# base.net
KiCad netlist of a schematic drawn in EAGLE
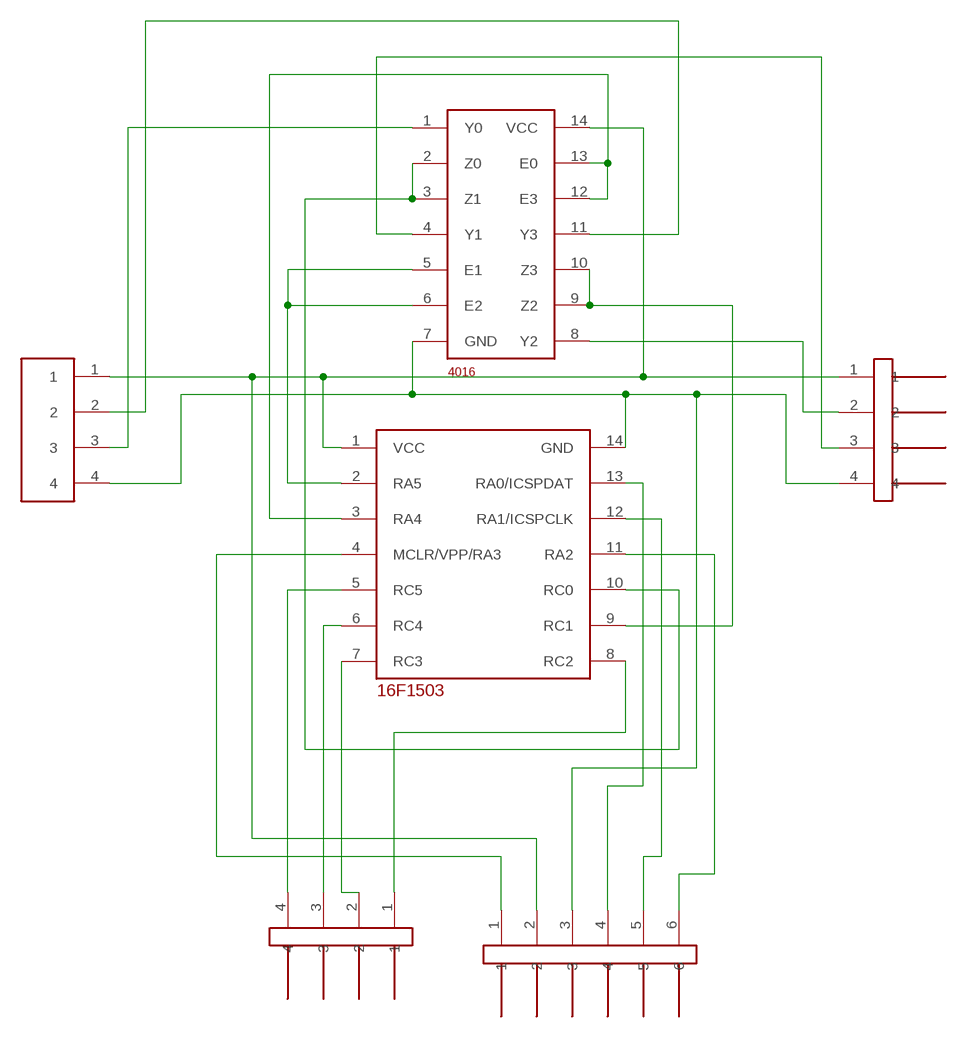
[diagram p0: schematic, sheet 1]

(export (version "E")
  (design (tool "Eeschema 10.0.6"))
  (components
    (comp (ref "U$1")
      (value "16F1503")
      (footprint "eagle-import:16F1503")
      (libsource (lib "eagle-import") (part "16F1503"))
    )
    (comp (ref "U$2")
      (value "4016")
      (footprint "eagle-import:SO14")
      (libsource (lib "eagle-import") (part "4016"))
    )
    (comp (ref "U$3")
      (value "JUMPER4")
      (footprint "eagle-import:JUMPER4")
      (libsource (lib "eagle-import") (part "JUMPER4"))
    )
    (comp (ref "U$4")
      (value "JUMPER4F")
      (footprint "eagle-import:JUMPER4F")
      (libsource (lib "eagle-import") (part "JUMPER4F"))
    )
    (comp (ref "U$5")
      (value "JUMPER4M")
      (footprint "eagle-import:JUMPER4M")
      (libsource (lib "eagle-import") (part "JUMPER4M"))
    )
    (comp (ref "U$6")
      (value "JUMPER6M")
      (footprint "eagle-import:JUMPER6M")
      (libsource (lib "eagle-import") (part "JUMPER6M"))
    )
  )
  (nets
    (net (code "1") (name "Net-(U$1-GND)") (class "Default")
      (node (ref "U$1") (pin "14") (pinfunction "GND_14") (pintype "power_in"))
      (node (ref "U$2") (pin "7") (pinfunction "GND_7") (pintype "bidirectional"))
      (node (ref "U$3") (pin "4") (pinfunction "4_4") (pintype "bidirectional"))
      (node (ref "U$4") (pin "4") (pinfunction "4_4") (pintype "bidirectional"))
      (node (ref "U$6") (pin "3") (pinfunction "3_3") (pintype "bidirectional"))
    )
    (net (code "2") (name "Net-(U$1-MCLR{slash}VPP{slash}RA3)") (class "Default")
      (node (ref "U$1") (pin "4") (pinfunction "MCLR/VPP/RA3_4") (pintype "bidirectional"))
      (node (ref "U$6") (pin "1") (pinfunction "1_1") (pintype "bidirectional"))
    )
    (net (code "3") (name "Net-(U$1-RA0{slash}ICSPDAT)") (class "Default")
      (node (ref "U$1") (pin "13") (pinfunction "RA0/ICSPDAT_13") (pintype "bidirectional"))
      (node (ref "U$6") (pin "4") (pinfunction "4_4") (pintype "bidirectional"))
    )
    (net (code "4") (name "Net-(U$1-RA1{slash}ICSPCLK)") (class "Default")
      (node (ref "U$1") (pin "12") (pinfunction "RA1/ICSPCLK_12") (pintype "bidirectional"))
      (node (ref "U$6") (pin "5") (pinfunction "5_5") (pintype "bidirectional"))
    )
    (net (code "5") (name "Net-(U$1-RA2)") (class "Default")
      (node (ref "U$1") (pin "11") (pinfunction "RA2_11") (pintype "bidirectional"))
      (node (ref "U$6") (pin "6") (pinfunction "6_6") (pintype "bidirectional"))
    )
    (net (code "6") (name "Net-(U$1-RA4)") (class "Default")
      (node (ref "U$1") (pin "3") (pinfunction "RA4_3") (pintype "bidirectional"))
      (node (ref "U$2") (pin "12") (pinfunction "E3_12") (pintype "bidirectional"))
      (node (ref "U$2") (pin "13") (pinfunction "E0_13") (pintype "bidirectional"))
    )
    (net (code "7") (name "Net-(U$1-RA5)") (class "Default")
      (node (ref "U$1") (pin "2") (pinfunction "RA5_2") (pintype "bidirectional"))
      (node (ref "U$2") (pin "5") (pinfunction "E1_5") (pintype "bidirectional"))
      (node (ref "U$2") (pin "6") (pinfunction "E2_6") (pintype "bidirectional"))
    )
    (net (code "8") (name "Net-(U$1-RC0)") (class "Default")
      (node (ref "U$1") (pin "10") (pinfunction "RC0_10") (pintype "bidirectional"))
      (node (ref "U$2") (pin "2") (pinfunction "Z0_2") (pintype "bidirectional"))
      (node (ref "U$2") (pin "3") (pinfunction "Z1_3") (pintype "bidirectional"))
    )
    (net (code "9") (name "Net-(U$1-RC1)") (class "Default")
      (node (ref "U$1") (pin "9") (pinfunction "RC1_9") (pintype "bidirectional"))
      (node (ref "U$2") (pin "10") (pinfunction "Z3_10") (pintype "bidirectional"))
      (node (ref "U$2") (pin "9") (pinfunction "Z2_9") (pintype "bidirectional"))
    )
    (net (code "10") (name "Net-(U$1-RC2)") (class "Default")
      (node (ref "U$1") (pin "8") (pinfunction "RC2_8") (pintype "bidirectional"))
      (node (ref "U$5") (pin "1") (pinfunction "1_1") (pintype "bidirectional"))
    )
    (net (code "11") (name "Net-(U$1-RC3)") (class "Default")
      (node (ref "U$1") (pin "7") (pinfunction "RC3_7") (pintype "bidirectional"))
      (node (ref "U$5") (pin "2") (pinfunction "2_2") (pintype "bidirectional"))
    )
    (net (code "12") (name "Net-(U$1-RC4)") (class "Default")
      (node (ref "U$1") (pin "6") (pinfunction "RC4_6") (pintype "bidirectional"))
      (node (ref "U$5") (pin "3") (pinfunction "3_3") (pintype "bidirectional"))
    )
    (net (code "13") (name "Net-(U$1-RC5)") (class "Default")
      (node (ref "U$1") (pin "5") (pinfunction "RC5_5") (pintype "bidirectional"))
      (node (ref "U$5") (pin "4") (pinfunction "4_4") (pintype "bidirectional"))
    )
    (net (code "14") (name "Net-(U$1-VCC)") (class "Default")
      (node (ref "U$1") (pin "1") (pinfunction "VCC_1") (pintype "power_in"))
      (node (ref "U$2") (pin "14") (pinfunction "VCC_14") (pintype "bidirectional"))
      (node (ref "U$3") (pin "1") (pinfunction "1_1") (pintype "bidirectional"))
      (node (ref "U$4") (pin "1") (pinfunction "1_1") (pintype "bidirectional"))
      (node (ref "U$6") (pin "2") (pinfunction "2_2") (pintype "bidirectional"))
    )
    (net (code "15") (name "Net-(U$2-Y0)") (class "Default")
      (node (ref "U$2") (pin "1") (pinfunction "Y0_1") (pintype "bidirectional"))
      (node (ref "U$4") (pin "3") (pinfunction "3_3") (pintype "bidirectional"))
    )
    (net (code "16") (name "Net-(U$2-Y1)") (class "Default")
      (node (ref "U$2") (pin "4") (pinfunction "Y1_4") (pintype "bidirectional"))
      (node (ref "U$3") (pin "3") (pinfunction "3_3") (pintype "bidirectional"))
    )
    (net (code "17") (name "Net-(U$2-Y2)") (class "Default")
      (node (ref "U$2") (pin "8") (pinfunction "Y2_8") (pintype "bidirectional"))
      (node (ref "U$3") (pin "2") (pinfunction "2_2") (pintype "bidirectional"))
    )
    (net (code "18") (name "Net-(U$2-Y3)") (class "Default")
      (node (ref "U$2") (pin "11") (pinfunction "Y3_11") (pintype "bidirectional"))
      (node (ref "U$4") (pin "2") (pinfunction "2_2") (pintype "bidirectional"))
    )
  )
)
